# PL-N823-01_Analog_Breakout.net
KiCad netlist of a schematic drawn in EAGLE
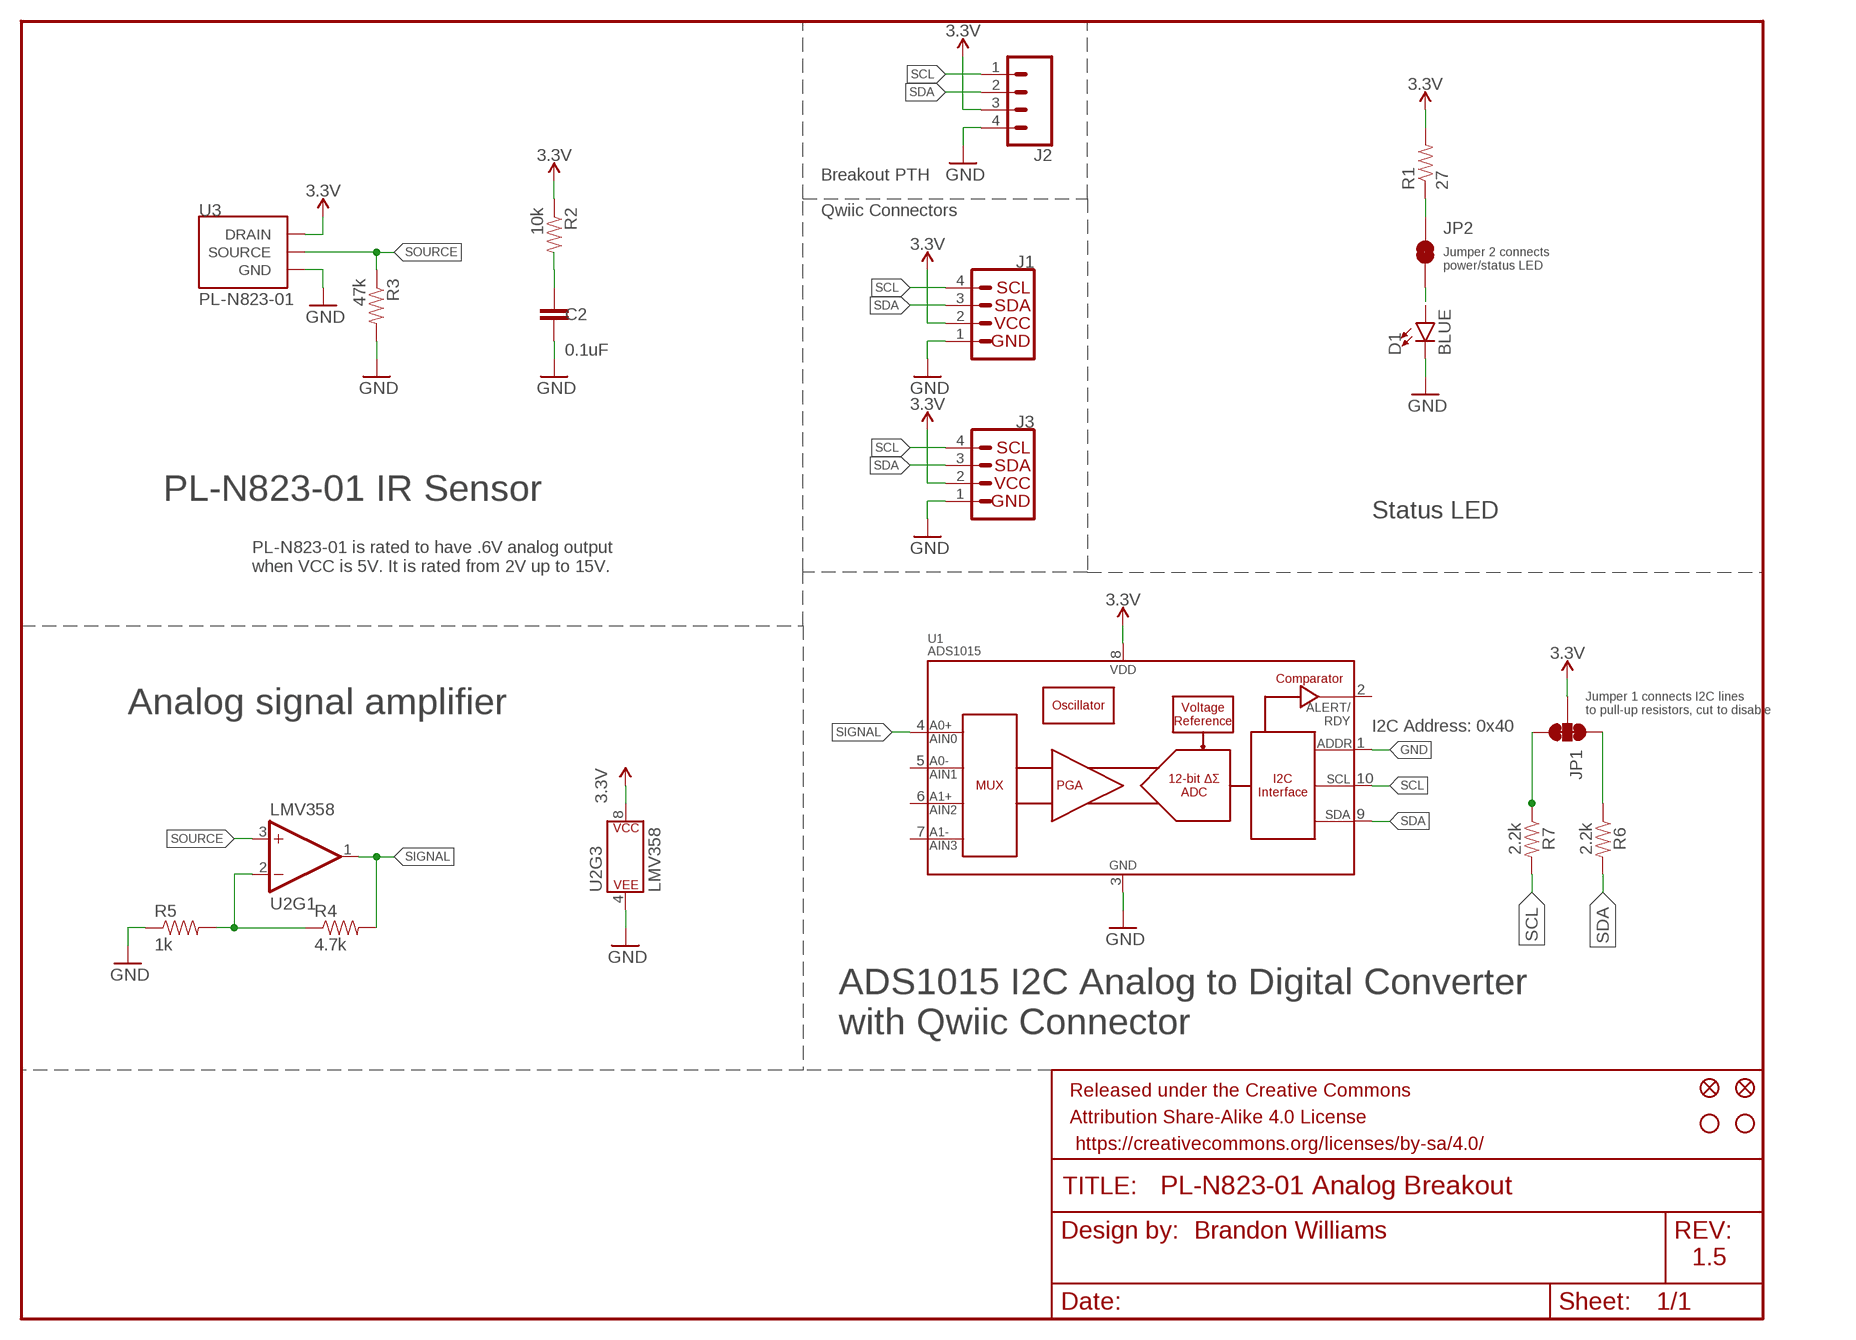
[diagram p0: schematic, sheet 1]

(export (version "E")
  (design (tool "Eeschema 10.0.6"))
  (components
    (comp (ref "C2")
      (value "0.1uF")
      (footprint "eagle-import:0603")
      (libsource (lib "eagle-import") (part "0.1UF-0603-25V-(+80/-20%)"))
    )
    (comp (ref "D1")
      (value "BLUE")
      (footprint "eagle-import:LED-0603")
      (libsource (lib "eagle-import") (part "LED-BLUE0603"))
    )
    (comp (ref "FD1")
      (value "FIDUCIALUFIDUCIAL")
      (footprint "eagle-import:FIDUCIAL-MICRO")
      (libsource (lib "eagle-import") (part "FIDUCIALUFIDUCIAL"))
    )
    (comp (ref "FD2")
      (value "FIDUCIALUFIDUCIAL")
      (footprint "eagle-import:FIDUCIAL-MICRO")
      (libsource (lib "eagle-import") (part "FIDUCIALUFIDUCIAL"))
    )
    (comp (ref "FRAME1")
      (value "FRAME-LETTERNO_PACKAGE")
      (footprint "eagle-import:DUMMY")
      (fields (field (name "DESIGNER") "Nobody"))
      (libsource (lib "eagle-import") (part "FRAME-LETTERNO_PACKAGE"))
    )
    (comp (ref "H1")
      (value "STAND-OFFTIGHT")
      (footprint "eagle-import:STAND-OFF-TIGHT")
      (libsource (lib "eagle-import") (part "STAND-OFFTIGHT"))
    )
    (comp (ref "H2")
      (value "STAND-OFFTIGHT")
      (footprint "eagle-import:STAND-OFF-TIGHT")
      (libsource (lib "eagle-import") (part "STAND-OFFTIGHT"))
    )
    (comp (ref "J1")
      (value "QWIIC_CONNECTORJS-1MM")
      (footprint "eagle-import:1X04_1MM_RA")
      (libsource (lib "eagle-import") (part "QWIIC_CONNECTORJS-1MM"))
    )
    (comp (ref "J2")
      (value "CONN_041X04_NO_SILK")
      (footprint "eagle-import:1X04_NO_SILK")
      (libsource (lib "eagle-import") (part "CONN_041X04_NO_SILK"))
    )
    (comp (ref "J3")
      (value "QWIIC_CONNECTORJS-1MM")
      (footprint "eagle-import:1X04_1MM_RA")
      (libsource (lib "eagle-import") (part "QWIIC_CONNECTORJS-1MM"))
    )
    (comp (ref "JP1")
      (value "JUMPER-SMT_3_2-NC_TRACE_SILK")
      (footprint "eagle-import:SMT-JUMPER_3_2-NC_TRACE_SILK")
      (libsource (lib "eagle-import") (part "JUMPER-SMT_3_2-NC_TRACE_SILK"))
    )
    (comp (ref "JP2")
      (value "JUMPER-SMT_2_NC_TRACE_SILK")
      (footprint "eagle-import:SMT-JUMPER_2_NC_TRACE_SILK")
      (libsource (lib "eagle-import") (part "JUMPER-SMT_2_NC_TRACE_SILK"))
    )
    (comp (ref "R1")
      (value "27")
      (footprint "eagle-import:0603")
      (libsource (lib "eagle-import") (part "27OHM-0603-1/10W-1%"))
    )
    (comp (ref "R2")
      (value "10k")
      (footprint "eagle-import:0603")
      (libsource (lib "eagle-import") (part "10KOHM-0603-1/10W-1%"))
    )
    (comp (ref "R3")
      (value "47k")
      (footprint "eagle-import:0603")
      (libsource (lib "eagle-import") (part "47KOHM-0603-1/10W-1%"))
    )
    (comp (ref "R4")
      (value "4.7k")
      (footprint "eagle-import:0603")
      (libsource (lib "eagle-import") (part "4.7KOHM-0603-1/10W-1%"))
    )
    (comp (ref "R5")
      (value "1k")
      (footprint "eagle-import:0603")
      (libsource (lib "eagle-import") (part "1KOHM-0603-1/10W-1%"))
    )
    (comp (ref "R6")
      (value "2.2k")
      (footprint "eagle-import:0603")
      (libsource (lib "eagle-import") (part "2.2KOHM-0603-1/10W-1%"))
    )
    (comp (ref "R7")
      (value "2.2k")
      (footprint "eagle-import:0603")
      (libsource (lib "eagle-import") (part "2.2KOHM-0603-1/10W-1%"))
    )
    (comp (ref "U1")
      (value "ADS1015")
      (footprint "eagle-import:MSOP10")
      (libsource (lib "eagle-import") (part "ADS1015"))
    )
    (comp (ref "U2")
      (value "LMV358")
      (footprint "eagle-import:SO08")
      (libsource (lib "eagle-import") (part "LMV358SOIC"))
    )
    (comp (ref "U3")
      (value "PL-N823-01")
      (footprint "eagle-import:PL-N823-01")
      (libsource (lib "eagle-import") (part "PL-N823-01"))
    )
  )
  (nets
    (net (code "1") (name "3.3V") (class "Default")
      (node (ref "J1") (pin "2") (pinfunction "VCC_2") (pintype "power_in"))
      (node (ref "J2") (pin "3") (pinfunction "3_3") (pintype "passive"))
      (node (ref "J3") (pin "2") (pinfunction "VCC_2") (pintype "power_in"))
      (node (ref "JP1") (pin "2") (pinfunction "2_2") (pintype "passive"))
      (node (ref "R1") (pin "2") (pinfunction "2_2") (pintype "passive"))
      (node (ref "R2") (pin "1") (pinfunction "1_1") (pintype "passive"))
      (node (ref "U1") (pin "8") (pinfunction "VDD_8") (pintype "bidirectional"))
      (node (ref "U2") (pin "8") (pinfunction "P$V+_8") (pintype "bidirectional"))
      (node (ref "U3") (pin "DRAIN") (pinfunction "DRAIN_DRAIN") (pintype "input"))
    )
    (net (code "2") (name "GND") (class "Default")
      (node (ref "C2") (pin "2") (pinfunction "2_2") (pintype "passive"))
      (node (ref "D1") (pin "C") (pinfunction "C_C") (pintype "passive"))
      (node (ref "J1") (pin "1") (pinfunction "GND_1") (pintype "power_in"))
      (node (ref "J2") (pin "4") (pinfunction "4_4") (pintype "passive"))
      (node (ref "J3") (pin "1") (pinfunction "GND_1") (pintype "power_in"))
      (node (ref "R3") (pin "2") (pinfunction "2_2") (pintype "passive"))
      (node (ref "R5") (pin "1") (pinfunction "1_1") (pintype "passive"))
      (node (ref "U1") (pin "1") (pinfunction "ADDR_1") (pintype "bidirectional"))
      (node (ref "U1") (pin "3") (pinfunction "VSS_3") (pintype "bidirectional"))
      (node (ref "U2") (pin "4") (pinfunction "P$V-_4") (pintype "bidirectional"))
      (node (ref "U3") (pin "GND@1") (pinfunction "GND_GND@1") (pintype "power_in"))
      (node (ref "U3") (pin "GND@2") (pinfunction "GND_GND@2") (pintype "power_in"))
    )
    (net (code "3") (name "Net-(C2-Pad1)") (class "Default")
      (node (ref "C2") (pin "1") (pinfunction "1_1") (pintype "passive"))
      (node (ref "R2") (pin "2") (pinfunction "2_2") (pintype "passive"))
    )
    (net (code "4") (name "Net-(D1-PadA)") (class "Default")
      (node (ref "D1") (pin "A") (pinfunction "A_A") (pintype "passive"))
      (node (ref "JP2") (pin "2") (pinfunction "2_2") (pintype "passive"))
    )
    (net (code "5") (name "Net-(JP1-Pad1)") (class "Default")
      (node (ref "JP1") (pin "1") (pinfunction "1_1") (pintype "passive"))
      (node (ref "R6") (pin "1") (pinfunction "1_1") (pintype "passive"))
    )
    (net (code "6") (name "Net-(JP1-Pad3)") (class "Default")
      (node (ref "JP1") (pin "3") (pinfunction "3_3") (pintype "passive"))
      (node (ref "R7") (pin "1") (pinfunction "1_1") (pintype "passive"))
    )
    (net (code "7") (name "Net-(JP2-Pad1)") (class "Default")
      (node (ref "JP2") (pin "1") (pinfunction "1_1") (pintype "passive"))
      (node (ref "R1") (pin "1") (pinfunction "1_1") (pintype "passive"))
    )
    (net (code "8") (name "Net-(U2A--IN)") (class "Default")
      (node (ref "R4") (pin "1") (pinfunction "1_1") (pintype "passive"))
      (node (ref "R5") (pin "2") (pinfunction "2_2") (pintype "passive"))
      (node (ref "U2") (pin "2") (pinfunction "-IN_2") (pintype "input"))
    )
    (net (code "9") (name "SCL") (class "Default")
      (node (ref "J1") (pin "4") (pinfunction "SCL_4") (pintype "passive"))
      (node (ref "J2") (pin "1") (pinfunction "1_1") (pintype "passive"))
      (node (ref "J3") (pin "4") (pinfunction "SCL_4") (pintype "passive"))
      (node (ref "R7") (pin "2") (pinfunction "2_2") (pintype "passive"))
      (node (ref "U1") (pin "10") (pinfunction "SCL_10") (pintype "bidirectional"))
    )
    (net (code "10") (name "SDA") (class "Default")
      (node (ref "J1") (pin "3") (pinfunction "SDA_3") (pintype "passive"))
      (node (ref "J2") (pin "2") (pinfunction "2_2") (pintype "passive"))
      (node (ref "J3") (pin "3") (pinfunction "SDA_3") (pintype "passive"))
      (node (ref "R6") (pin "2") (pinfunction "2_2") (pintype "passive"))
      (node (ref "U1") (pin "9") (pinfunction "SDA_9") (pintype "bidirectional"))
    )
    (net (code "11") (name "SIGNAL") (class "Default")
      (node (ref "R4") (pin "2") (pinfunction "2_2") (pintype "passive"))
      (node (ref "U1") (pin "4") (pinfunction "AIN0_4") (pintype "bidirectional"))
      (node (ref "U2") (pin "1") (pinfunction "OUT_1") (pintype "output"))
    )
    (net (code "12") (name "SOURCE") (class "Default")
      (node (ref "R3") (pin "1") (pinfunction "1_1") (pintype "passive"))
      (node (ref "U2") (pin "3") (pinfunction "+IN_3") (pintype "input"))
      (node (ref "U3") (pin "SOURCE") (pinfunction "SOURCE_SOURCE") (pintype "output"))
    )
    (net (code "13") (name "unconnected-(U1-AIN1-Pad5)") (class "Default")
      (node (ref "U1") (pin "5") (pinfunction "AIN1_5") (pintype "bidirectional"))
    )
    (net (code "14") (name "unconnected-(U1-AIN2-Pad6)") (class "Default")
      (node (ref "U1") (pin "6") (pinfunction "AIN2_6") (pintype "bidirectional"))
    )
    (net (code "15") (name "unconnected-(U1-AIN3-Pad7)") (class "Default")
      (node (ref "U1") (pin "7") (pinfunction "AIN3_7") (pintype "bidirectional"))
    )
    (net (code "16") (name "unconnected-(U1-ALERT{slash}RDY-Pad2)") (class "Default")
      (node (ref "U1") (pin "2") (pinfunction "ALERT/RDY_2") (pintype "bidirectional"))
    )
  )
)
